# ESP32.net
KiCad netlist of a schematic drawn in Altium Designer
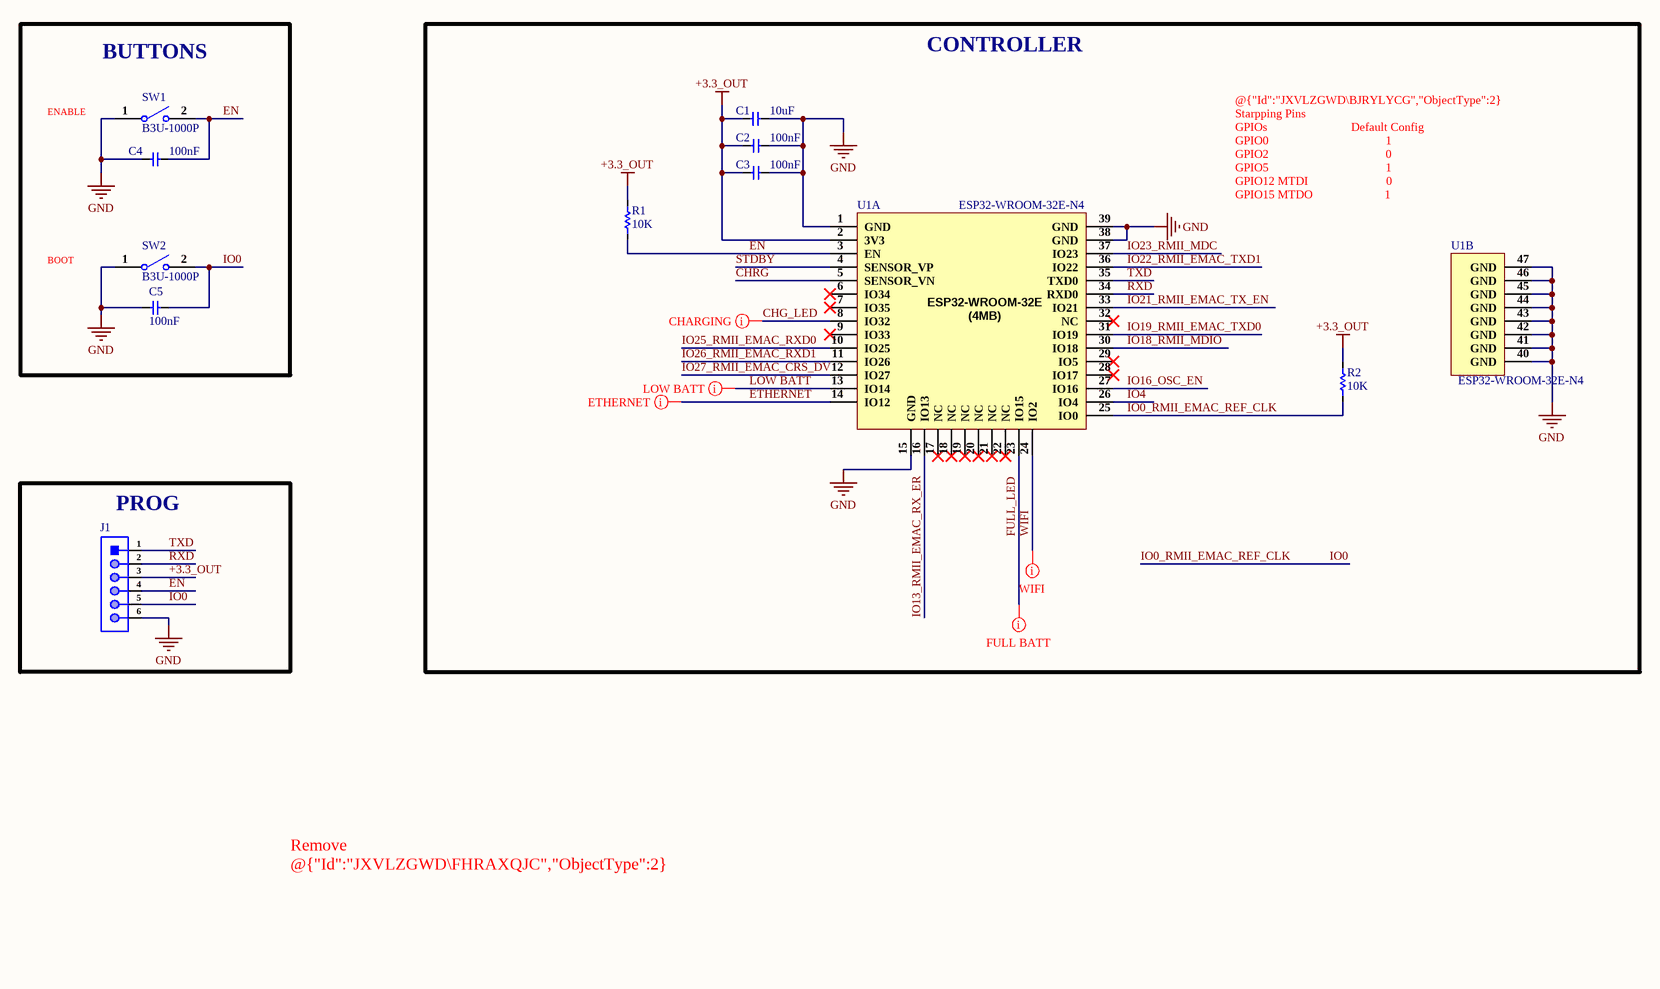
[diagram p0: ESP32.SchDoc]

(export (version "E")
  (design (tool "Eeschema 10.0.6"))
  (components
    (comp (ref "C1")
      (value "10uF")
      (footprint "Cap-0603")
      (description "CAP CER 10UF 16V X5R 0603")
      (fields
        (field (name "MANUFACTURER") "Yageo")
        (field (name "MANUFACTURER PART NUMBER") "CC0603KRX5R7BB106")
      )
      (libsource (lib "eSpark Libraries") (part "CC0603KRX5R7BB106"))
    )
    (comp (ref "C2")
      (value "100nF")
      (footprint "cap-0402")
      (description "CAP CER 0.1UF 50V X7R 0402")
      (fields
        (field (name "MANUFACTURER") "TDK")
        (field (name "MANUFACTURER PART NUMBER") "C1005X7R1H104KT000F")
      )
      (libsource (lib "eSpark Libraries") (part "C1005X7R1H104KT000F"))
    )
    (comp (ref "C3")
      (value "100nF")
      (footprint "cap-0402")
      (description "CAP CER 0.1UF 50V X7R 0402")
      (fields
        (field (name "MANUFACTURER") "TDK")
        (field (name "MANUFACTURER PART NUMBER") "C1005X7R1H104KT000F")
      )
      (libsource (lib "eSpark Libraries") (part "C1005X7R1H104KT000F"))
    )
    (comp (ref "C4")
      (value "100nF")
      (footprint "cap-0402")
      (description "CAP CER 0.1UF 50V X7R 0402")
      (fields
        (field (name "MANUFACTURER") "TDK")
        (field (name "MANUFACTURER PART NUMBER") "C1005X7R1H104KT000F")
      )
      (libsource (lib "eSpark Libraries") (part "C1005X7R1H104KT000F"))
    )
    (comp (ref "C5")
      (value "100nF")
      (footprint "cap-0402")
      (description "CAP CER 0.1UF 50V X7R 0402")
      (fields
        (field (name "MANUFACTURER") "TDK")
        (field (name "MANUFACTURER PART NUMBER") "C1005X7R1H104KT000F")
      )
      (libsource (lib "eSpark Libraries") (part "C1005X7R1H104KT000F"))
    )
    (comp (ref "J1")
      (value "X6511WV-06H-C60D30")
      (footprint "HDR1X6_")
      (fields (field (name "MANUFACTURER") "XKB") (field (name "LCSC PART NUMBER") "C706878"))
      (libsource (lib "eSpark Libraries") (part "X6511WV-06H-C60D30"))
    )
    (comp (ref "R1")
      (value "10K")
      (footprint "Res-0402")
      (description "RES 10K OHM 1% 1/16W 0402")
      (fields
        (field (name "MANUFACTURER") "Yageo")
        (field (name "MANUFACTURER PART NUMBER") "RC0402FR-0710KL")
      )
      (libsource (lib "eSpark Libraries") (part "RC0402FR-0710KL"))
    )
    (comp (ref "R2")
      (value "10K")
      (footprint "Res-0402")
      (description "RES 10K OHM 1% 1/16W 0402")
      (fields
        (field (name "MANUFACTURER") "Yageo")
        (field (name "MANUFACTURER PART NUMBER") "RC0402FR-0710KL")
      )
      (libsource (lib "eSpark Libraries") (part "RC0402FR-0710KL"))
    )
    (comp (ref "SW1")
      (value "B3U-1000P")
      (footprint "B3U-1000P")
      (description "SWITCH TACTILE SPST-NO 0.05A 12V")
      (fields (field (name "MANUFACTURER") "Omron") (field (name "LCSC PART NUMBER") "C231329"))
      (libsource (lib "eSpark Libraries") (part "B3U-1000P"))
    )
    (comp (ref "SW2")
      (value "B3U-1000P")
      (footprint "B3U-1000P")
      (description "SWITCH TACTILE SPST-NO 0.05A 12V")
      (fields (field (name "MANUFACTURER") "Omron") (field (name "LCSC PART NUMBER") "C231329"))
      (libsource (lib "eSpark Libraries") (part "B3U-1000P"))
    )
    (comp (ref "U1")
      (value "ESP32-WROOM-32E-N4")
      (footprint "38-SMD Module")
      (description "RX TXRX MOD WIFI TRACE ANT SMD")
      (fields (field (name "MANUFACTURER") "Espressif Systems") (field (name "LCSC PART NUMBER") "C701341"))
      (libsource (lib "eSpark Libraries") (part "ESP32-WROOM-32E-N4"))
    )
  )
  (nets
    (net (code "1") (name "+3.3_OUT") (class "Default")
      (node (ref "C1") (pin "1") (pinfunction "1_1") (pintype "passive"))
      (node (ref "C2") (pin "2") (pinfunction "2_2") (pintype "passive"))
      (node (ref "C3") (pin "2") (pinfunction "2_2") (pintype "passive"))
      (node (ref "J1") (pin "3") (pinfunction "3_3") (pintype "passive"))
      (node (ref "R1") (pin "2") (pinfunction "2_2") (pintype "passive"))
      (node (ref "R2") (pin "2") (pinfunction "2_2") (pintype "passive"))
      (node (ref "U1") (pin "2") (pinfunction "3V3_2") (pintype "passive"))
    )
    (net (code "2") (name "/CHG_LED") (class "Default")
      (node (ref "U1") (pin "8") (pinfunction "IO32_8") (pintype "passive"))
    )
    (net (code "3") (name "/CHRG") (class "Default")
      (node (ref "U1") (pin "5") (pinfunction "SENSOR_VN_5") (pintype "passive"))
    )
    (net (code "4") (name "/EN") (class "Default")
      (node (ref "C4") (pin "1") (pinfunction "1_1") (pintype "passive"))
      (node (ref "J1") (pin "4") (pinfunction "4_4") (pintype "passive"))
      (node (ref "R1") (pin "1") (pinfunction "1_1") (pintype "passive"))
      (node (ref "SW1") (pin "2") (pinfunction "2_2") (pintype "passive"))
      (node (ref "U1") (pin "3") (pinfunction "EN_3") (pintype "passive"))
    )
    (net (code "5") (name "/ETHERNET") (class "Default")
      (node (ref "U1") (pin "14") (pinfunction "IO12_14") (pintype "passive"))
    )
    (net (code "6") (name "/FULL_LED") (class "Default")
      (node (ref "U1") (pin "23") (pinfunction "IO15_23") (pintype "passive"))
    )
    (net (code "7") (name "/IO0") (class "Default")
      (node (ref "C5") (pin "1") (pinfunction "1_1") (pintype "passive"))
      (node (ref "J1") (pin "5") (pinfunction "5_5") (pintype "passive"))
      (node (ref "R2") (pin "1") (pinfunction "1_1") (pintype "passive"))
      (node (ref "SW2") (pin "2") (pinfunction "2_2") (pintype "passive"))
      (node (ref "U1") (pin "25") (pinfunction "IO0_25") (pintype "passive"))
    )
    (net (code "8") (name "/IO4") (class "Default")
      (node (ref "U1") (pin "26") (pinfunction "IO4_26") (pintype "passive"))
    )
    (net (code "9") (name "/IO13_RMII_EMAC_RX_ER") (class "Default")
      (node (ref "U1") (pin "16") (pinfunction "IO13_16") (pintype "passive"))
    )
    (net (code "10") (name "/IO16_OSC_EN") (class "Default")
      (node (ref "U1") (pin "27") (pinfunction "IO16_27") (pintype "passive"))
    )
    (net (code "11") (name "/IO18_RMII_MDIO") (class "Default")
      (node (ref "U1") (pin "30") (pinfunction "IO18_30") (pintype "passive"))
    )
    (net (code "12") (name "/IO19_RMII_EMAC_TXD0") (class "Default")
      (node (ref "U1") (pin "31") (pinfunction "IO19_31") (pintype "passive"))
    )
    (net (code "13") (name "/IO21_RMII_EMAC_TX_EN") (class "Default")
      (node (ref "U1") (pin "33") (pinfunction "IO21_33") (pintype "passive"))
    )
    (net (code "14") (name "/IO22_RMII_EMAC_TXD1") (class "Default")
      (node (ref "U1") (pin "36") (pinfunction "IO22_36") (pintype "passive"))
    )
    (net (code "15") (name "/IO23_RMII_MDC") (class "Default")
      (node (ref "U1") (pin "37") (pinfunction "IO23_37") (pintype "passive"))
    )
    (net (code "16") (name "/IO25_RMII_EMAC_RXD0") (class "Default")
      (node (ref "U1") (pin "10") (pinfunction "IO25_10") (pintype "passive"))
    )
    (net (code "17") (name "/IO26_RMII_EMAC_RXD1") (class "Default")
      (node (ref "U1") (pin "11") (pinfunction "IO26_11") (pintype "passive"))
    )
    (net (code "18") (name "/IO27_RMII_EMAC_CRS_DV") (class "Default")
      (node (ref "U1") (pin "12") (pinfunction "IO27_12") (pintype "passive"))
    )
    (net (code "19") (name "/LOW BATT") (class "Default")
      (node (ref "U1") (pin "13") (pinfunction "IO14_13") (pintype "passive"))
    )
    (net (code "20") (name "/RXD") (class "Default")
      (node (ref "J1") (pin "2") (pinfunction "2_2") (pintype "passive"))
      (node (ref "U1") (pin "34") (pinfunction "RXD0_34") (pintype "passive"))
    )
    (net (code "21") (name "/STDBY") (class "Default")
      (node (ref "U1") (pin "4") (pinfunction "SENSOR_VP_4") (pintype "passive"))
    )
    (net (code "22") (name "/TXD") (class "Default")
      (node (ref "J1") (pin "1") (pinfunction "1_1") (pintype "passive"))
      (node (ref "U1") (pin "35") (pinfunction "TXD0_35") (pintype "passive"))
    )
    (net (code "23") (name "/WIFI") (class "Default")
      (node (ref "U1") (pin "24") (pinfunction "IO2_24") (pintype "passive"))
    )
    (net (code "24") (name "GND") (class "Default")
      (node (ref "C1") (pin "2") (pinfunction "2_2") (pintype "passive"))
      (node (ref "C2") (pin "1") (pinfunction "1_1") (pintype "passive"))
      (node (ref "C3") (pin "1") (pinfunction "1_1") (pintype "passive"))
      (node (ref "C4") (pin "2") (pinfunction "2_2") (pintype "passive"))
      (node (ref "C5") (pin "2") (pinfunction "2_2") (pintype "passive"))
      (node (ref "J1") (pin "6") (pinfunction "6_6") (pintype "passive"))
      (node (ref "SW1") (pin "1") (pinfunction "1_1") (pintype "passive"))
      (node (ref "SW2") (pin "1") (pinfunction "1_1") (pintype "passive"))
      (node (ref "U1") (pin "1") (pinfunction "GND_1") (pintype "passive"))
      (node (ref "U1") (pin "15") (pinfunction "GND_15") (pintype "passive"))
      (node (ref "U1") (pin "38") (pinfunction "GND_38") (pintype "passive"))
      (node (ref "U1") (pin "39") (pinfunction "GND_39") (pintype "passive"))
      (node (ref "U1") (pin "40") (pinfunction "GND_40") (pintype "passive"))
      (node (ref "U1") (pin "41") (pinfunction "GND_41") (pintype "passive"))
      (node (ref "U1") (pin "42") (pinfunction "GND_42") (pintype "passive"))
      (node (ref "U1") (pin "43") (pinfunction "GND_43") (pintype "passive"))
      (node (ref "U1") (pin "44") (pinfunction "GND_44") (pintype "passive"))
      (node (ref "U1") (pin "45") (pinfunction "GND_45") (pintype "passive"))
      (node (ref "U1") (pin "46") (pinfunction "GND_46") (pintype "passive"))
      (node (ref "U1") (pin "47") (pinfunction "GND_47") (pintype "passive"))
    )
    (net (code "25") (name "unconnected-(U1A-IO5-Pad29)") (class "Default")
      (node (ref "U1") (pin "29") (pinfunction "IO5_29") (pintype "passive+no_connect"))
    )
    (net (code "26") (name "unconnected-(U1A-IO17-Pad28)") (class "Default")
      (node (ref "U1") (pin "28") (pinfunction "IO17_28") (pintype "passive+no_connect"))
    )
    (net (code "27") (name "unconnected-(U1A-IO33-Pad9)") (class "Default")
      (node (ref "U1") (pin "9") (pinfunction "IO33_9") (pintype "passive+no_connect"))
    )
    (net (code "28") (name "unconnected-(U1A-IO34-Pad6)") (class "Default")
      (node (ref "U1") (pin "6") (pinfunction "IO34_6") (pintype "passive+no_connect"))
    )
    (net (code "29") (name "unconnected-(U1A-IO35-Pad7)") (class "Default")
      (node (ref "U1") (pin "7") (pinfunction "IO35_7") (pintype "passive+no_connect"))
    )
    (net (code "30") (name "unconnected-(U1A-NC-Pad17)") (class "Default")
      (node (ref "U1") (pin "17") (pinfunction "NC_17") (pintype "passive+no_connect"))
    )
    (net (code "31") (name "unconnected-(U1A-NC-Pad18)") (class "Default")
      (node (ref "U1") (pin "18") (pinfunction "NC_18") (pintype "passive+no_connect"))
    )
    (net (code "32") (name "unconnected-(U1A-NC-Pad19)") (class "Default")
      (node (ref "U1") (pin "19") (pinfunction "NC_19") (pintype "passive+no_connect"))
    )
    (net (code "33") (name "unconnected-(U1A-NC-Pad20)") (class "Default")
      (node (ref "U1") (pin "20") (pinfunction "NC_20") (pintype "passive+no_connect"))
    )
    (net (code "34") (name "unconnected-(U1A-NC-Pad21)") (class "Default")
      (node (ref "U1") (pin "21") (pinfunction "NC_21") (pintype "passive+no_connect"))
    )
    (net (code "35") (name "unconnected-(U1A-NC-Pad22)") (class "Default")
      (node (ref "U1") (pin "22") (pinfunction "NC_22") (pintype "passive+no_connect"))
    )
    (net (code "36") (name "unconnected-(U1A-NC-Pad32)") (class "Default")
      (node (ref "U1") (pin "32") (pinfunction "NC_32") (pintype "passive+no_connect"))
    )
  )
)
